# schematic.net
KiCad netlist of a schematic drawn in EAGLE
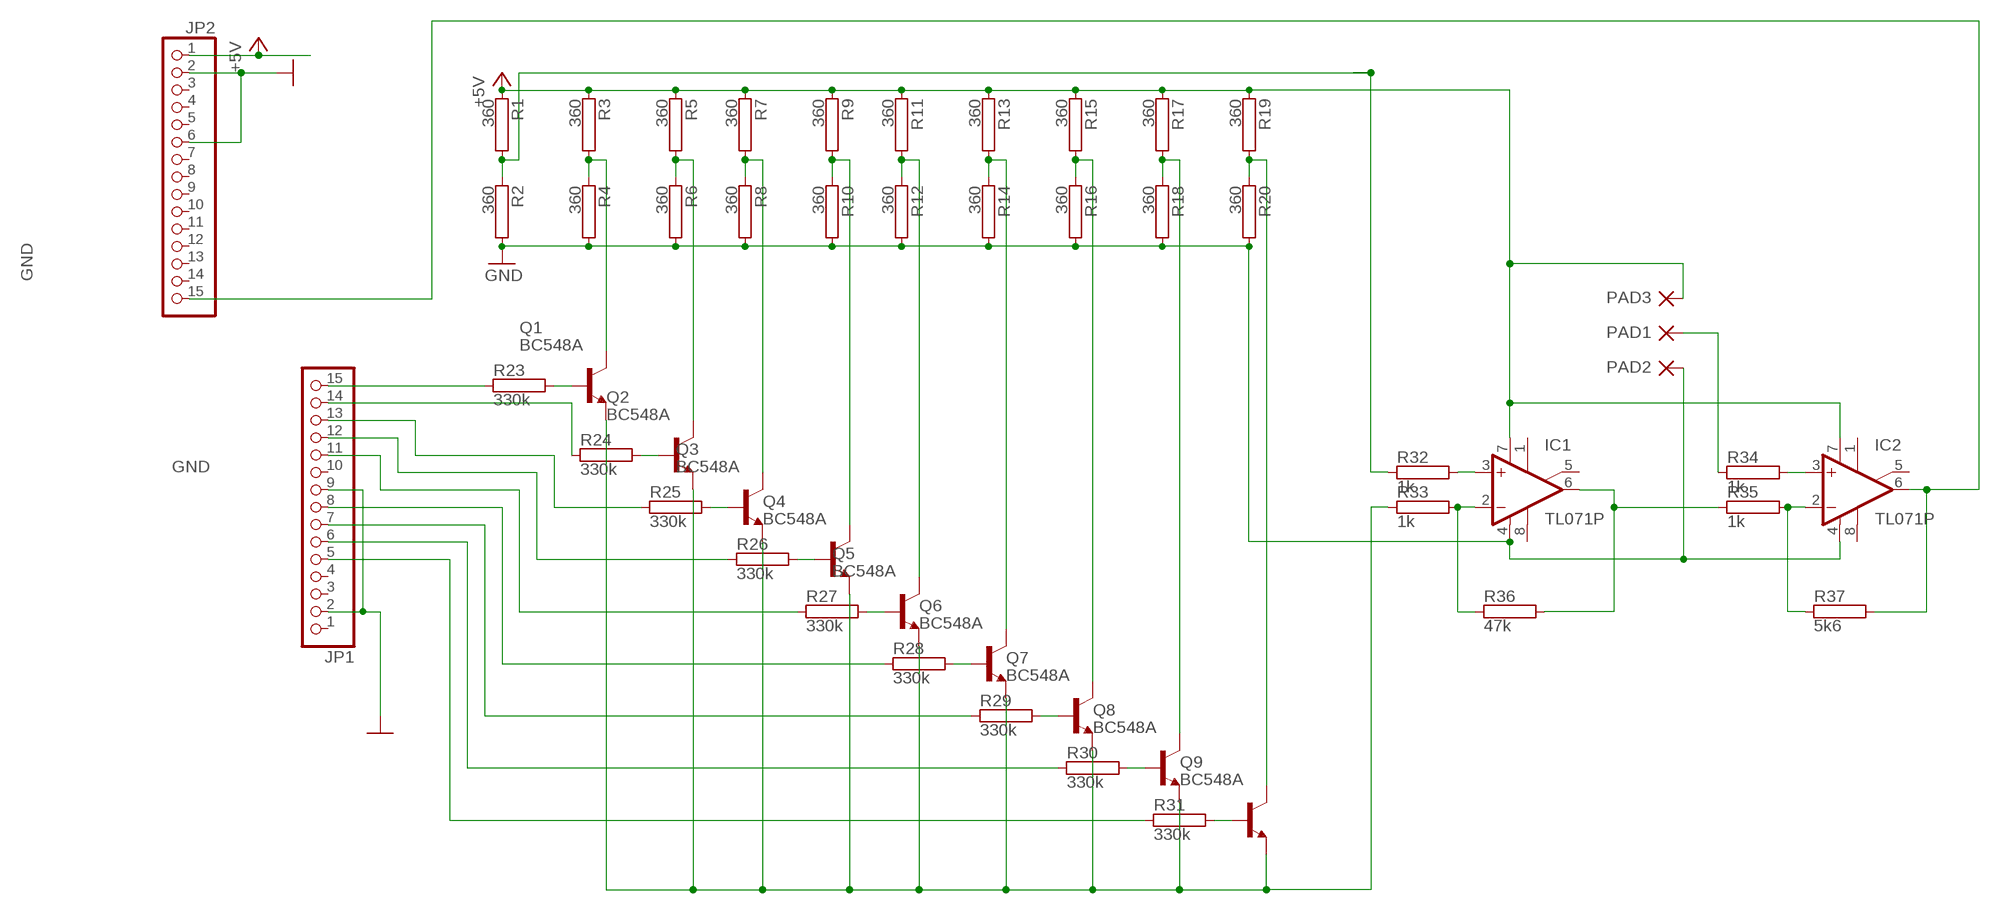
[diagram p0: schematic, sheet 1]

(export (version "E")
  (design (tool "Eeschema 10.0.6"))
  (components
    (comp (ref "IC1")
      (value "TL071P")
      (footprint "eagle-import:DIL08")
      (libsource (lib "eagle-import") (part "TL071P"))
    )
    (comp (ref "IC2")
      (value "TL071P")
      (footprint "eagle-import:DIL08")
      (libsource (lib "eagle-import") (part "TL071P"))
    )
    (comp (ref "JP1")
      (value "PINHD-1X15")
      (footprint "eagle-import:1X15")
      (libsource (lib "eagle-import") (part "PINHD-1X15"))
    )
    (comp (ref "JP2")
      (value "PINHD-1X15")
      (footprint "eagle-import:1X15")
      (libsource (lib "eagle-import") (part "PINHD-1X15"))
    )
    (comp (ref "PAD1")
      (value "WIREPADSMD5-1,8")
      (footprint "eagle-import:5-1,8")
      (libsource (lib "eagle-import") (part "WIREPADSMD5-1,8"))
    )
    (comp (ref "PAD2")
      (value "WIREPADSMD5-1,8")
      (footprint "eagle-import:5-1,8")
      (libsource (lib "eagle-import") (part "WIREPADSMD5-1,8"))
    )
    (comp (ref "PAD3")
      (value "WIREPADSMD5-1,8")
      (footprint "eagle-import:5-1,8")
      (libsource (lib "eagle-import") (part "WIREPADSMD5-1,8"))
    )
    (comp (ref "Q1")
      (value "BC548A")
      (footprint "eagle-import:TO92-EBC")
      (libsource (lib "eagle-import") (part "BC548A"))
    )
    (comp (ref "Q2")
      (value "BC548A")
      (footprint "eagle-import:TO92-EBC")
      (libsource (lib "eagle-import") (part "BC548A"))
    )
    (comp (ref "Q3")
      (value "BC548A")
      (footprint "eagle-import:TO92-EBC")
      (libsource (lib "eagle-import") (part "BC548A"))
    )
    (comp (ref "Q4")
      (value "BC548A")
      (footprint "eagle-import:TO92-EBC")
      (libsource (lib "eagle-import") (part "BC548A"))
    )
    (comp (ref "Q5")
      (value "BC548A")
      (footprint "eagle-import:TO92-EBC")
      (libsource (lib "eagle-import") (part "BC548A"))
    )
    (comp (ref "Q6")
      (value "BC548A")
      (footprint "eagle-import:TO92-EBC")
      (libsource (lib "eagle-import") (part "BC548A"))
    )
    (comp (ref "Q7")
      (value "BC548A")
      (footprint "eagle-import:TO92-EBC")
      (libsource (lib "eagle-import") (part "BC548A"))
    )
    (comp (ref "Q8")
      (value "BC548A")
      (footprint "eagle-import:TO92-EBC")
      (libsource (lib "eagle-import") (part "BC548A"))
    )
    (comp (ref "Q9")
      (value "BC548A")
      (footprint "eagle-import:TO92-EBC")
      (libsource (lib "eagle-import") (part "BC548A"))
    )
    (comp (ref "R1")
      (value "360")
      (footprint "eagle-import:RS1_4")
      (fields (field (name "MF") "OHMITE") (field (name "MPN") "RRS1K0"))
      (libsource (lib "eagle-import") (part "RRS1/4"))
    )
    (comp (ref "R2")
      (value "360")
      (footprint "eagle-import:RS1_4")
      (fields (field (name "MF") "OHMITE") (field (name "MPN") "RRS1K0"))
      (libsource (lib "eagle-import") (part "RRS1/4"))
    )
    (comp (ref "R3")
      (value "360")
      (footprint "eagle-import:RS1_4")
      (fields (field (name "MF") "OHMITE") (field (name "MPN") "RRS1K0"))
      (libsource (lib "eagle-import") (part "RRS1/4"))
    )
    (comp (ref "R4")
      (value "360")
      (footprint "eagle-import:RS1_4")
      (fields (field (name "MF") "OHMITE") (field (name "MPN") "RRS1K0"))
      (libsource (lib "eagle-import") (part "RRS1/4"))
    )
    (comp (ref "R5")
      (value "360")
      (footprint "eagle-import:RS1_4")
      (fields (field (name "MF") "OHMITE") (field (name "MPN") "RRS1K0"))
      (libsource (lib "eagle-import") (part "RRS1/4"))
    )
    (comp (ref "R6")
      (value "360")
      (footprint "eagle-import:RS1_4")
      (fields (field (name "MF") "OHMITE") (field (name "MPN") "RRS1K0"))
      (libsource (lib "eagle-import") (part "RRS1/4"))
    )
    (comp (ref "R7")
      (value "360")
      (footprint "eagle-import:RS1_4")
      (fields (field (name "MF") "OHMITE") (field (name "MPN") "RRS1K0"))
      (libsource (lib "eagle-import") (part "RRS1/4"))
    )
    (comp (ref "R8")
      (value "360")
      (footprint "eagle-import:RS1_4")
      (fields (field (name "MF") "OHMITE") (field (name "MPN") "RRS1K0"))
      (libsource (lib "eagle-import") (part "RRS1/4"))
    )
    (comp (ref "R9")
      (value "360")
      (footprint "eagle-import:RS1_4")
      (fields (field (name "MF") "OHMITE") (field (name "MPN") "RRS1K0"))
      (libsource (lib "eagle-import") (part "RRS1/4"))
    )
    (comp (ref "R10")
      (value "360")
      (footprint "eagle-import:RS1_4")
      (fields (field (name "MF") "OHMITE") (field (name "MPN") "RRS1K0"))
      (libsource (lib "eagle-import") (part "RRS1/4"))
    )
    (comp (ref "R11")
      (value "360")
      (footprint "eagle-import:RS1_4")
      (fields (field (name "MF") "OHMITE") (field (name "MPN") "RRS1K0"))
      (libsource (lib "eagle-import") (part "RRS1/4"))
    )
    (comp (ref "R12")
      (value "360")
      (footprint "eagle-import:RS1_4")
      (fields (field (name "MF") "OHMITE") (field (name "MPN") "RRS1K0"))
      (libsource (lib "eagle-import") (part "RRS1/4"))
    )
    (comp (ref "R13")
      (value "360")
      (footprint "eagle-import:RS1_4")
      (fields (field (name "MF") "OHMITE") (field (name "MPN") "RRS1K0"))
      (libsource (lib "eagle-import") (part "RRS1/4"))
    )
    (comp (ref "R14")
      (value "360")
      (footprint "eagle-import:RS1_4")
      (fields (field (name "MF") "OHMITE") (field (name "MPN") "RRS1K0"))
      (libsource (lib "eagle-import") (part "RRS1/4"))
    )
    (comp (ref "R15")
      (value "360")
      (footprint "eagle-import:RS1_4")
      (fields (field (name "MF") "OHMITE") (field (name "MPN") "RRS1K0"))
      (libsource (lib "eagle-import") (part "RRS1/4"))
    )
    (comp (ref "R16")
      (value "360")
      (footprint "eagle-import:RS1_4")
      (fields (field (name "MF") "OHMITE") (field (name "MPN") "RRS1K0"))
      (libsource (lib "eagle-import") (part "RRS1/4"))
    )
    (comp (ref "R17")
      (value "360")
      (footprint "eagle-import:RS1_4")
      (fields (field (name "MF") "OHMITE") (field (name "MPN") "RRS1K0"))
      (libsource (lib "eagle-import") (part "RRS1/4"))
    )
    (comp (ref "R18")
      (value "360")
      (footprint "eagle-import:RS1_4")
      (fields (field (name "MF") "OHMITE") (field (name "MPN") "RRS1K0"))
      (libsource (lib "eagle-import") (part "RRS1/4"))
    )
    (comp (ref "R19")
      (value "360")
      (footprint "eagle-import:RS1_4")
      (fields (field (name "MF") "OHMITE") (field (name "MPN") "RRS1K0"))
      (libsource (lib "eagle-import") (part "RRS1/4"))
    )
    (comp (ref "R20")
      (value "360")
      (footprint "eagle-import:RS1_4")
      (fields (field (name "MF") "OHMITE") (field (name "MPN") "RRS1K0"))
      (libsource (lib "eagle-import") (part "RRS1/4"))
    )
    (comp (ref "R23")
      (value "330k")
      (footprint "eagle-import:RS1_4")
      (fields (field (name "MF") "OHMITE") (field (name "MPN") "RRS1K0"))
      (libsource (lib "eagle-import") (part "RRS1/4"))
    )
    (comp (ref "R24")
      (value "330k")
      (footprint "eagle-import:RS1_4")
      (fields (field (name "MF") "OHMITE") (field (name "MPN") "RRS1K0"))
      (libsource (lib "eagle-import") (part "RRS1/4"))
    )
    (comp (ref "R25")
      (value "330k")
      (footprint "eagle-import:RS1_4")
      (fields (field (name "MF") "OHMITE") (field (name "MPN") "RRS1K0"))
      (libsource (lib "eagle-import") (part "RRS1/4"))
    )
    (comp (ref "R26")
      (value "330k")
      (footprint "eagle-import:RS1_4")
      (fields (field (name "MF") "OHMITE") (field (name "MPN") "RRS1K0"))
      (libsource (lib "eagle-import") (part "RRS1/4"))
    )
    (comp (ref "R27")
      (value "330k")
      (footprint "eagle-import:RS1_4")
      (fields (field (name "MF") "OHMITE") (field (name "MPN") "RRS1K0"))
      (libsource (lib "eagle-import") (part "RRS1/4"))
    )
    (comp (ref "R28")
      (value "330k")
      (footprint "eagle-import:RS1_4")
      (fields (field (name "MF") "OHMITE") (field (name "MPN") "RRS1K0"))
      (libsource (lib "eagle-import") (part "RRS1/4"))
    )
    (comp (ref "R29")
      (value "330k")
      (footprint "eagle-import:RS1_4")
      (fields (field (name "MF") "OHMITE") (field (name "MPN") "RRS1K0"))
      (libsource (lib "eagle-import") (part "RRS1/4"))
    )
    (comp (ref "R30")
      (value "330k")
      (footprint "eagle-import:RS1_4")
      (fields (field (name "MF") "OHMITE") (field (name "MPN") "RRS1K0"))
      (libsource (lib "eagle-import") (part "RRS1/4"))
    )
    (comp (ref "R31")
      (value "330k")
      (footprint "eagle-import:RS1_4")
      (fields (field (name "MF") "OHMITE") (field (name "MPN") "RRS1K0"))
      (libsource (lib "eagle-import") (part "RRS1/4"))
    )
    (comp (ref "R32")
      (value "1k")
      (footprint "eagle-import:RS1_4")
      (fields (field (name "MF") "OHMITE") (field (name "MPN") "RRS1K0"))
      (libsource (lib "eagle-import") (part "RRS1/4"))
    )
    (comp (ref "R33")
      (value "1k")
      (footprint "eagle-import:RS1_4")
      (fields (field (name "MF") "OHMITE") (field (name "MPN") "RRS1K0"))
      (libsource (lib "eagle-import") (part "RRS1/4"))
    )
    (comp (ref "R34")
      (value "1k")
      (footprint "eagle-import:RS1_4")
      (fields (field (name "MF") "OHMITE") (field (name "MPN") "RRS1K0"))
      (libsource (lib "eagle-import") (part "RRS1/4"))
    )
    (comp (ref "R35")
      (value "1k")
      (footprint "eagle-import:RS1_4")
      (fields (field (name "MF") "OHMITE") (field (name "MPN") "RRS1K0"))
      (libsource (lib "eagle-import") (part "RRS1/4"))
    )
    (comp (ref "R36")
      (value "47k")
      (footprint "eagle-import:RS1_4")
      (fields (field (name "MF") "OHMITE") (field (name "MPN") "RRS1K0"))
      (libsource (lib "eagle-import") (part "RRS1/4"))
    )
    (comp (ref "R37")
      (value "5k6")
      (footprint "eagle-import:RS1_4")
      (fields (field (name "MF") "OHMITE") (field (name "MPN") "RRS1K0"))
      (libsource (lib "eagle-import") (part "RRS1/4"))
    )
  )
  (nets
    (net (code "1") (name "+5V") (class "Default")
      (node (ref "IC1") (pin "7") (pinfunction "V+_7") (pintype "power_in"))
      (node (ref "IC2") (pin "7") (pinfunction "V+_7") (pintype "power_in"))
      (node (ref "JP2") (pin "1") (pinfunction "1_1") (pintype "passive"))
      (node (ref "PAD3") (pin "1") (pinfunction "P_1") (pintype "passive"))
      (node (ref "R1") (pin "1") (pinfunction "1_1") (pintype "passive"))
      (node (ref "R11") (pin "1") (pinfunction "1_1") (pintype "passive"))
      (node (ref "R13") (pin "1") (pinfunction "1_1") (pintype "passive"))
      (node (ref "R15") (pin "1") (pinfunction "1_1") (pintype "passive"))
      (node (ref "R17") (pin "1") (pinfunction "1_1") (pintype "passive"))
      (node (ref "R19") (pin "1") (pinfunction "1_1") (pintype "passive"))
      (node (ref "R3") (pin "1") (pinfunction "1_1") (pintype "passive"))
      (node (ref "R5") (pin "1") (pinfunction "1_1") (pintype "passive"))
      (node (ref "R7") (pin "1") (pinfunction "1_1") (pintype "passive"))
      (node (ref "R9") (pin "1") (pinfunction "1_1") (pintype "passive"))
    )
    (net (code "2") (name "GND") (class "Default")
      (node (ref "IC1") (pin "4") (pinfunction "V-_4") (pintype "power_in"))
      (node (ref "IC2") (pin "4") (pinfunction "V-_4") (pintype "power_in"))
      (node (ref "JP1") (pin "2") (pinfunction "2_2") (pintype "passive"))
      (node (ref "JP1") (pin "9") (pinfunction "9_9") (pintype "passive"))
      (node (ref "JP2") (pin "2") (pinfunction "2_2") (pintype "passive"))
      (node (ref "JP2") (pin "6") (pinfunction "6_6") (pintype "passive"))
      (node (ref "PAD2") (pin "1") (pinfunction "P_1") (pintype "passive"))
      (node (ref "R10") (pin "2") (pinfunction "2_2") (pintype "passive"))
      (node (ref "R12") (pin "2") (pinfunction "2_2") (pintype "passive"))
      (node (ref "R14") (pin "2") (pinfunction "2_2") (pintype "passive"))
      (node (ref "R16") (pin "2") (pinfunction "2_2") (pintype "passive"))
      (node (ref "R18") (pin "2") (pinfunction "2_2") (pintype "passive"))
      (node (ref "R2") (pin "2") (pinfunction "2_2") (pintype "passive"))
      (node (ref "R20") (pin "2") (pinfunction "2_2") (pintype "passive"))
      (node (ref "R4") (pin "2") (pinfunction "2_2") (pintype "passive"))
      (node (ref "R6") (pin "2") (pinfunction "2_2") (pintype "passive"))
      (node (ref "R8") (pin "2") (pinfunction "2_2") (pintype "passive"))
    )
    (net (code "3") (name "Net-(IC1-+IN)") (class "Default")
      (node (ref "IC1") (pin "3") (pinfunction "+IN_3") (pintype "input"))
      (node (ref "R32") (pin "2") (pinfunction "2_2") (pintype "passive"))
    )
    (net (code "4") (name "Net-(IC1--IN)") (class "Default")
      (node (ref "IC1") (pin "2") (pinfunction "-IN_2") (pintype "input"))
      (node (ref "R33") (pin "2") (pinfunction "2_2") (pintype "passive"))
      (node (ref "R36") (pin "1") (pinfunction "1_1") (pintype "passive"))
    )
    (net (code "5") (name "Net-(IC1-OUT)") (class "Default")
      (node (ref "IC1") (pin "6") (pinfunction "OUT_6") (pintype "output"))
      (node (ref "R35") (pin "1") (pinfunction "1_1") (pintype "passive"))
      (node (ref "R36") (pin "2") (pinfunction "2_2") (pintype "passive"))
    )
    (net (code "6") (name "Net-(IC2-+IN)") (class "Default")
      (node (ref "IC2") (pin "3") (pinfunction "+IN_3") (pintype "input"))
      (node (ref "R34") (pin "2") (pinfunction "2_2") (pintype "passive"))
    )
    (net (code "7") (name "Net-(IC2--IN)") (class "Default")
      (node (ref "IC2") (pin "2") (pinfunction "-IN_2") (pintype "input"))
      (node (ref "R35") (pin "2") (pinfunction "2_2") (pintype "passive"))
      (node (ref "R37") (pin "1") (pinfunction "1_1") (pintype "passive"))
    )
    (net (code "8") (name "Net-(IC2-OUT)") (class "Default")
      (node (ref "IC2") (pin "6") (pinfunction "OUT_6") (pintype "output"))
      (node (ref "JP2") (pin "15") (pinfunction "15_15") (pintype "passive"))
      (node (ref "R37") (pin "2") (pinfunction "2_2") (pintype "passive"))
    )
    (net (code "9") (name "Net-(JP1-Pad5)") (class "Default")
      (node (ref "JP1") (pin "5") (pinfunction "5_5") (pintype "passive"))
      (node (ref "R31") (pin "1") (pinfunction "1_1") (pintype "passive"))
    )
    (net (code "10") (name "Net-(JP1-Pad6)") (class "Default")
      (node (ref "JP1") (pin "6") (pinfunction "6_6") (pintype "passive"))
      (node (ref "R30") (pin "1") (pinfunction "1_1") (pintype "passive"))
    )
    (net (code "11") (name "Net-(JP1-Pad7)") (class "Default")
      (node (ref "JP1") (pin "7") (pinfunction "7_7") (pintype "passive"))
      (node (ref "R29") (pin "1") (pinfunction "1_1") (pintype "passive"))
    )
    (net (code "12") (name "Net-(JP1-Pad8)") (class "Default")
      (node (ref "JP1") (pin "8") (pinfunction "8_8") (pintype "passive"))
      (node (ref "R28") (pin "1") (pinfunction "1_1") (pintype "passive"))
    )
    (net (code "13") (name "Net-(JP1-Pad11)") (class "Default")
      (node (ref "JP1") (pin "11") (pinfunction "11_11") (pintype "passive"))
      (node (ref "R27") (pin "1") (pinfunction "1_1") (pintype "passive"))
    )
    (net (code "14") (name "Net-(JP1-Pad12)") (class "Default")
      (node (ref "JP1") (pin "12") (pinfunction "12_12") (pintype "passive"))
      (node (ref "R26") (pin "1") (pinfunction "1_1") (pintype "passive"))
    )
    (net (code "15") (name "Net-(JP1-Pad13)") (class "Default")
      (node (ref "JP1") (pin "13") (pinfunction "13_13") (pintype "passive"))
      (node (ref "R25") (pin "1") (pinfunction "1_1") (pintype "passive"))
    )
    (net (code "16") (name "Net-(JP1-Pad14)") (class "Default")
      (node (ref "JP1") (pin "14") (pinfunction "14_14") (pintype "passive"))
      (node (ref "R24") (pin "1") (pinfunction "1_1") (pintype "passive"))
    )
    (net (code "17") (name "Net-(JP1-Pad15)") (class "Default")
      (node (ref "JP1") (pin "15") (pinfunction "15_15") (pintype "passive"))
      (node (ref "R23") (pin "1") (pinfunction "1_1") (pintype "passive"))
    )
    (net (code "18") (name "Net-(PAD1-P)") (class "Default")
      (node (ref "PAD1") (pin "1") (pinfunction "P_1") (pintype "passive"))
      (node (ref "R34") (pin "1") (pinfunction "1_1") (pintype "passive"))
    )
    (net (code "19") (name "Net-(Q1-PadB)") (class "Default")
      (node (ref "Q1") (pin "B") (pinfunction "B_B") (pintype "passive"))
      (node (ref "R23") (pin "2") (pinfunction "2_2") (pintype "passive"))
    )
    (net (code "20") (name "Net-(Q1-PadC)") (class "Default")
      (node (ref "Q1") (pin "C") (pinfunction "C_C") (pintype "passive"))
      (node (ref "R3") (pin "2") (pinfunction "2_2") (pintype "passive"))
      (node (ref "R4") (pin "1") (pinfunction "1_1") (pintype "passive"))
    )
    (net (code "21") (name "Net-(Q1-PadE)") (class "Default")
      (node (ref "Q1") (pin "E") (pinfunction "E_E") (pintype "passive"))
      (node (ref "Q2") (pin "E") (pinfunction "E_E") (pintype "passive"))
      (node (ref "Q3") (pin "E") (pinfunction "E_E") (pintype "passive"))
      (node (ref "Q4") (pin "E") (pinfunction "E_E") (pintype "passive"))
      (node (ref "Q5") (pin "E") (pinfunction "E_E") (pintype "passive"))
      (node (ref "Q6") (pin "E") (pinfunction "E_E") (pintype "passive"))
      (node (ref "Q7") (pin "E") (pinfunction "E_E") (pintype "passive"))
      (node (ref "Q8") (pin "E") (pinfunction "E_E") (pintype "passive"))
      (node (ref "Q9") (pin "E") (pinfunction "E_E") (pintype "passive"))
      (node (ref "R33") (pin "1") (pinfunction "1_1") (pintype "passive"))
    )
    (net (code "22") (name "Net-(Q2-PadB)") (class "Default")
      (node (ref "Q2") (pin "B") (pinfunction "B_B") (pintype "passive"))
      (node (ref "R24") (pin "2") (pinfunction "2_2") (pintype "passive"))
    )
    (net (code "23") (name "Net-(Q2-PadC)") (class "Default")
      (node (ref "Q2") (pin "C") (pinfunction "C_C") (pintype "passive"))
      (node (ref "R5") (pin "2") (pinfunction "2_2") (pintype "passive"))
      (node (ref "R6") (pin "1") (pinfunction "1_1") (pintype "passive"))
    )
    (net (code "24") (name "Net-(Q3-PadB)") (class "Default")
      (node (ref "Q3") (pin "B") (pinfunction "B_B") (pintype "passive"))
      (node (ref "R25") (pin "2") (pinfunction "2_2") (pintype "passive"))
    )
    (net (code "25") (name "Net-(Q3-PadC)") (class "Default")
      (node (ref "Q3") (pin "C") (pinfunction "C_C") (pintype "passive"))
      (node (ref "R7") (pin "2") (pinfunction "2_2") (pintype "passive"))
      (node (ref "R8") (pin "1") (pinfunction "1_1") (pintype "passive"))
    )
    (net (code "26") (name "Net-(Q4-PadB)") (class "Default")
      (node (ref "Q4") (pin "B") (pinfunction "B_B") (pintype "passive"))
      (node (ref "R26") (pin "2") (pinfunction "2_2") (pintype "passive"))
    )
    (net (code "27") (name "Net-(Q4-PadC)") (class "Default")
      (node (ref "Q4") (pin "C") (pinfunction "C_C") (pintype "passive"))
      (node (ref "R10") (pin "1") (pinfunction "1_1") (pintype "passive"))
      (node (ref "R9") (pin "2") (pinfunction "2_2") (pintype "passive"))
    )
    (net (code "28") (name "Net-(Q5-PadB)") (class "Default")
      (node (ref "Q5") (pin "B") (pinfunction "B_B") (pintype "passive"))
      (node (ref "R27") (pin "2") (pinfunction "2_2") (pintype "passive"))
    )
    (net (code "29") (name "Net-(Q5-PadC)") (class "Default")
      (node (ref "Q5") (pin "C") (pinfunction "C_C") (pintype "passive"))
      (node (ref "R11") (pin "2") (pinfunction "2_2") (pintype "passive"))
      (node (ref "R12") (pin "1") (pinfunction "1_1") (pintype "passive"))
    )
    (net (code "30") (name "Net-(Q6-PadB)") (class "Default")
      (node (ref "Q6") (pin "B") (pinfunction "B_B") (pintype "passive"))
      (node (ref "R28") (pin "2") (pinfunction "2_2") (pintype "passive"))
    )
    (net (code "31") (name "Net-(Q6-PadC)") (class "Default")
      (node (ref "Q6") (pin "C") (pinfunction "C_C") (pintype "passive"))
      (node (ref "R13") (pin "2") (pinfunction "2_2") (pintype "passive"))
      (node (ref "R14") (pin "1") (pinfunction "1_1") (pintype "passive"))
    )
    (net (code "32") (name "Net-(Q7-PadB)") (class "Default")
      (node (ref "Q7") (pin "B") (pinfunction "B_B") (pintype "passive"))
      (node (ref "R29") (pin "2") (pinfunction "2_2") (pintype "passive"))
    )
    (net (code "33") (name "Net-(Q7-PadC)") (class "Default")
      (node (ref "Q7") (pin "C") (pinfunction "C_C") (pintype "passive"))
      (node (ref "R15") (pin "2") (pinfunction "2_2") (pintype "passive"))
      (node (ref "R16") (pin "1") (pinfunction "1_1") (pintype "passive"))
    )
    (net (code "34") (name "Net-(Q8-PadB)") (class "Default")
      (node (ref "Q8") (pin "B") (pinfunction "B_B") (pintype "passive"))
      (node (ref "R30") (pin "2") (pinfunction "2_2") (pintype "passive"))
    )
    (net (code "35") (name "Net-(Q8-PadC)") (class "Default")
      (node (ref "Q8") (pin "C") (pinfunction "C_C") (pintype "passive"))
      (node (ref "R17") (pin "2") (pinfunction "2_2") (pintype "passive"))
      (node (ref "R18") (pin "1") (pinfunction "1_1") (pintype "passive"))
    )
    (net (code "36") (name "Net-(Q9-PadB)") (class "Default")
      (node (ref "Q9") (pin "B") (pinfunction "B_B") (pintype "passive"))
      (node (ref "R31") (pin "2") (pinfunction "2_2") (pintype "passive"))
    )
    (net (code "37") (name "Net-(Q9-PadC)") (class "Default")
      (node (ref "Q9") (pin "C") (pinfunction "C_C") (pintype "passive"))
      (node (ref "R19") (pin "2") (pinfunction "2_2") (pintype "passive"))
      (node (ref "R20") (pin "1") (pinfunction "1_1") (pintype "passive"))
    )
    (net (code "38") (name "Net-(R1-Pad2)") (class "Default")
      (node (ref "R1") (pin "2") (pinfunction "2_2") (pintype "passive"))
      (node (ref "R2") (pin "1") (pinfunction "1_1") (pintype "passive"))
      (node (ref "R32") (pin "1") (pinfunction "1_1") (pintype "passive"))
    )
    (net (code "39") (name "unconnected-(IC1-ON1-Pad1)") (class "Default")
      (node (ref "IC1") (pin "1") (pinfunction "ON1_1") (pintype "passive"))
    )
    (net (code "40") (name "unconnected-(IC1-ON2-Pad5)") (class "Default")
      (node (ref "IC1") (pin "5") (pinfunction "ON2_5") (pintype "passive"))
    )
    (net (code "41") (name "unconnected-(IC1-OPT-Pad8)") (class "Default")
      (node (ref "IC1") (pin "8") (pinfunction "OPT_8") (pintype "passive"))
    )
    (net (code "42") (name "unconnected-(IC2-ON1-Pad1)") (class "Default")
      (node (ref "IC2") (pin "1") (pinfunction "ON1_1") (pintype "passive"))
    )
    (net (code "43") (name "unconnected-(IC2-ON2-Pad5)") (class "Default")
      (node (ref "IC2") (pin "5") (pinfunction "ON2_5") (pintype "passive"))
    )
    (net (code "44") (name "unconnected-(IC2-OPT-Pad8)") (class "Default")
      (node (ref "IC2") (pin "8") (pinfunction "OPT_8") (pintype "passive"))
    )
    (net (code "45") (name "unconnected-(JP1-Pad1)") (class "Default")
      (node (ref "JP1") (pin "1") (pinfunction "1_1") (pintype "passive"))
    )
    (net (code "46") (name "unconnected-(JP1-Pad3)") (class "Default")
      (node (ref "JP1") (pin "3") (pinfunction "3_3") (pintype "passive"))
    )
    (net (code "47") (name "unconnected-(JP1-Pad4)") (class "Default")
      (node (ref "JP1") (pin "4") (pinfunction "4_4") (pintype "passive"))
    )
    (net (code "48") (name "unconnected-(JP1-Pad10)") (class "Default")
      (node (ref "JP1") (pin "10") (pinfunction "10_10") (pintype "passive"))
    )
    (net (code "49") (name "unconnected-(JP2-Pad3)") (class "Default")
      (node (ref "JP2") (pin "3") (pinfunction "3_3") (pintype "passive"))
    )
    (net (code "50") (name "unconnected-(JP2-Pad4)") (class "Default")
      (node (ref "JP2") (pin "4") (pinfunction "4_4") (pintype "passive"))
    )
    (net (code "51") (name "unconnected-(JP2-Pad5)") (class "Default")
      (node (ref "JP2") (pin "5") (pinfunction "5_5") (pintype "passive"))
    )
    (net (code "52") (name "unconnected-(JP2-Pad7)") (class "Default")
      (node (ref "JP2") (pin "7") (pinfunction "7_7") (pintype "passive"))
    )
    (net (code "53") (name "unconnected-(JP2-Pad8)") (class "Default")
      (node (ref "JP2") (pin "8") (pinfunction "8_8") (pintype "passive"))
    )
    (net (code "54") (name "unconnected-(JP2-Pad9)") (class "Default")
      (node (ref "JP2") (pin "9") (pinfunction "9_9") (pintype "passive"))
    )
    (net (code "55") (name "unconnected-(JP2-Pad10)") (class "Default")
      (node (ref "JP2") (pin "10") (pinfunction "10_10") (pintype "passive"))
    )
    (net (code "56") (name "unconnected-(JP2-Pad11)") (class "Default")
      (node (ref "JP2") (pin "11") (pinfunction "11_11") (pintype "passive"))
    )
    (net (code "57") (name "unconnected-(JP2-Pad12)") (class "Default")
      (node (ref "JP2") (pin "12") (pinfunction "12_12") (pintype "passive"))
    )
    (net (code "58") (name "unconnected-(JP2-Pad13)") (class "Default")
      (node (ref "JP2") (pin "13") (pinfunction "13_13") (pintype "passive"))
    )
    (net (code "59") (name "unconnected-(JP2-Pad14)") (class "Default")
      (node (ref "JP2") (pin "14") (pinfunction "14_14") (pintype "passive"))
    )
  )
)
